# PFC_BUCK_BOOST.net
KiCad netlist of a schematic drawn in Altium Designer
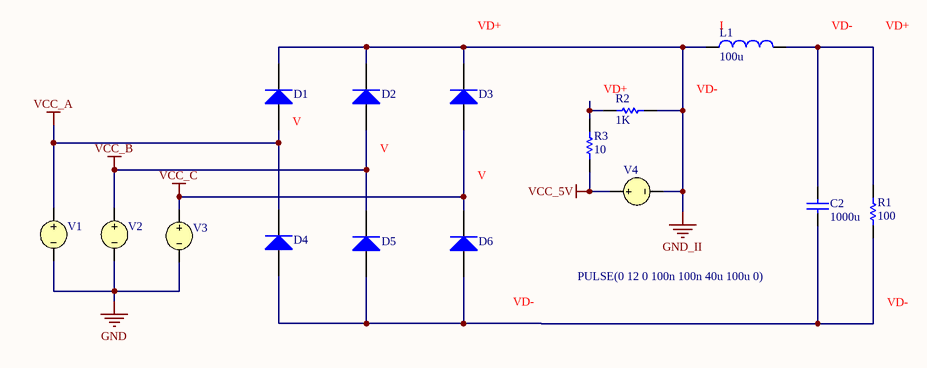
[diagram p0: PFC_BUCK_BOOST.SchDoc]

(export (version "E")
  (design (tool "Eeschema 10.0.6"))
  (components
    (comp (ref "C2")
      (value "1000u")
      (description "Capacitor")
      (libsource (lib "Simulation Generic Components") (part "Capacitor"))
    )
    (comp (ref "D1") (value "Diode") (libsource (lib "Simulation Generic Components") (part "Diode")))
    (comp (ref "D2") (value "Diode") (libsource (lib "Simulation Generic Components") (part "Diode")))
    (comp (ref "D3") (value "Diode") (libsource (lib "Simulation Generic Components") (part "Diode")))
    (comp (ref "D4") (value "Diode") (libsource (lib "Simulation Generic Components") (part "Diode")))
    (comp (ref "D5") (value "Diode") (libsource (lib "Simulation Generic Components") (part "Diode")))
    (comp (ref "D6") (value "Diode") (libsource (lib "Simulation Generic Components") (part "Diode")))
    (comp (ref "L1")
      (value "100u")
      (description "Inductor")
      (libsource (lib "Simulation Generic Components") (part "Inductor"))
    )
    (comp (ref "R1")
      (value "100")
      (description "Resistor")
      (libsource (lib "Simulation Generic Components") (part "Resistor"))
    )
    (comp (ref "R2")
      (value "1K")
      (description "Resistor")
      (libsource (lib "Simulation Generic Components") (part "Resistor"))
    )
    (comp (ref "R3")
      (value "10")
      (description "Resistor")
      (libsource (lib "Simulation Generic Components") (part "Resistor"))
    )
    (comp (ref "V1")
      (value "SIN(0 315 50 0 0 0)")
      (description "Voltage Source")
      (fields (field (name "PUBLISHER") "Altium Limited"))
      (libsource (lib "Simulation Generic Components") (part "VSRC"))
    )
    (comp (ref "V2")
      (value "SIN(0 315 50 0 0 120)")
      (description "Voltage Source")
      (fields (field (name "PUBLISHER") "Altium Limited"))
      (libsource (lib "Simulation Generic Components") (part "VSRC"))
    )
    (comp (ref "V3")
      (value "SIN(0 315 50 0 0 240)")
      (description "Voltage Source")
      (fields (field (name "PUBLISHER") "Altium Limited"))
      (libsource (lib "Simulation Generic Components") (part "VSRC"))
    )
    (comp (ref "V4")
      (value "PULSE(0 12 0 100n 100n 40u 100u 0)")
      (description "Voltage Source")
      (fields (field (name "PUBLISHER") "Altium Limited"))
      (libsource (lib "Simulation Generic Components") (part "VSRC"))
    )
  )
  (nets
    (net (code "1") (name "GND") (class "Default")
      (node (ref "V1") (pin "2") (pinfunction "2_2") (pintype "passive"))
      (node (ref "V2") (pin "2") (pinfunction "2_2") (pintype "passive"))
      (node (ref "V3") (pin "2") (pinfunction "2_2") (pintype "passive"))
    )
    (net (code "2") (name "GND_II") (class "Default")
      (node (ref "D1") (pin "2") (pinfunction "K_2") (pintype "passive"))
      (node (ref "D2") (pin "2") (pinfunction "K_2") (pintype "passive"))
      (node (ref "D3") (pin "2") (pinfunction "K_2") (pintype "passive"))
      (node (ref "L1") (pin "1") (pinfunction "1_1") (pintype "passive"))
      (node (ref "R2") (pin "1") (pinfunction "1_1") (pintype "passive"))
      (node (ref "V4") (pin "2") (pinfunction "2_2") (pintype "passive"))
    )
    (net (code "3") (name "Net-(C2-Pad2)") (class "Default")
      (node (ref "C2") (pin "2") (pinfunction "2_2") (pintype "passive"))
      (node (ref "L1") (pin "2") (pinfunction "2_2") (pintype "passive"))
      (node (ref "R1") (pin "2") (pinfunction "2_2") (pintype "passive"))
    )
    (net (code "4") (name "Net-(D4-A)") (class "Default")
      (node (ref "C2") (pin "1") (pinfunction "1_1") (pintype "passive"))
      (node (ref "D4") (pin "1") (pinfunction "A_1") (pintype "passive"))
      (node (ref "D5") (pin "1") (pinfunction "A_1") (pintype "passive"))
      (node (ref "D6") (pin "1") (pinfunction "A_1") (pintype "passive"))
      (node (ref "R1") (pin "1") (pinfunction "1_1") (pintype "passive"))
    )
    (net (code "5") (name "Net-(R2-Pad2)") (class "Default")
      (node (ref "R2") (pin "2") (pinfunction "2_2") (pintype "passive"))
      (node (ref "R3") (pin "2") (pinfunction "2_2") (pintype "passive"))
    )
    (net (code "6") (name "VCC_5V") (class "Default")
      (node (ref "R3") (pin "1") (pinfunction "1_1") (pintype "passive"))
      (node (ref "V4") (pin "1") (pinfunction "1_1") (pintype "passive"))
    )
    (net (code "7") (name "VCC_A") (class "Default")
      (node (ref "D1") (pin "1") (pinfunction "A_1") (pintype "passive"))
      (node (ref "D4") (pin "2") (pinfunction "K_2") (pintype "passive"))
      (node (ref "V1") (pin "1") (pinfunction "1_1") (pintype "passive"))
    )
    (net (code "8") (name "VCC_B") (class "Default")
      (node (ref "D2") (pin "1") (pinfunction "A_1") (pintype "passive"))
      (node (ref "D5") (pin "2") (pinfunction "K_2") (pintype "passive"))
      (node (ref "V2") (pin "1") (pinfunction "1_1") (pintype "passive"))
    )
    (net (code "9") (name "VCC_C") (class "Default")
      (node (ref "D3") (pin "1") (pinfunction "A_1") (pintype "passive"))
      (node (ref "D6") (pin "2") (pinfunction "K_2") (pintype "passive"))
      (node (ref "V3") (pin "1") (pinfunction "1_1") (pintype "passive"))
    )
  )
)
